# 3_-MCU_MAIN.net
KiCad netlist of a schematic drawn in Altium Designer
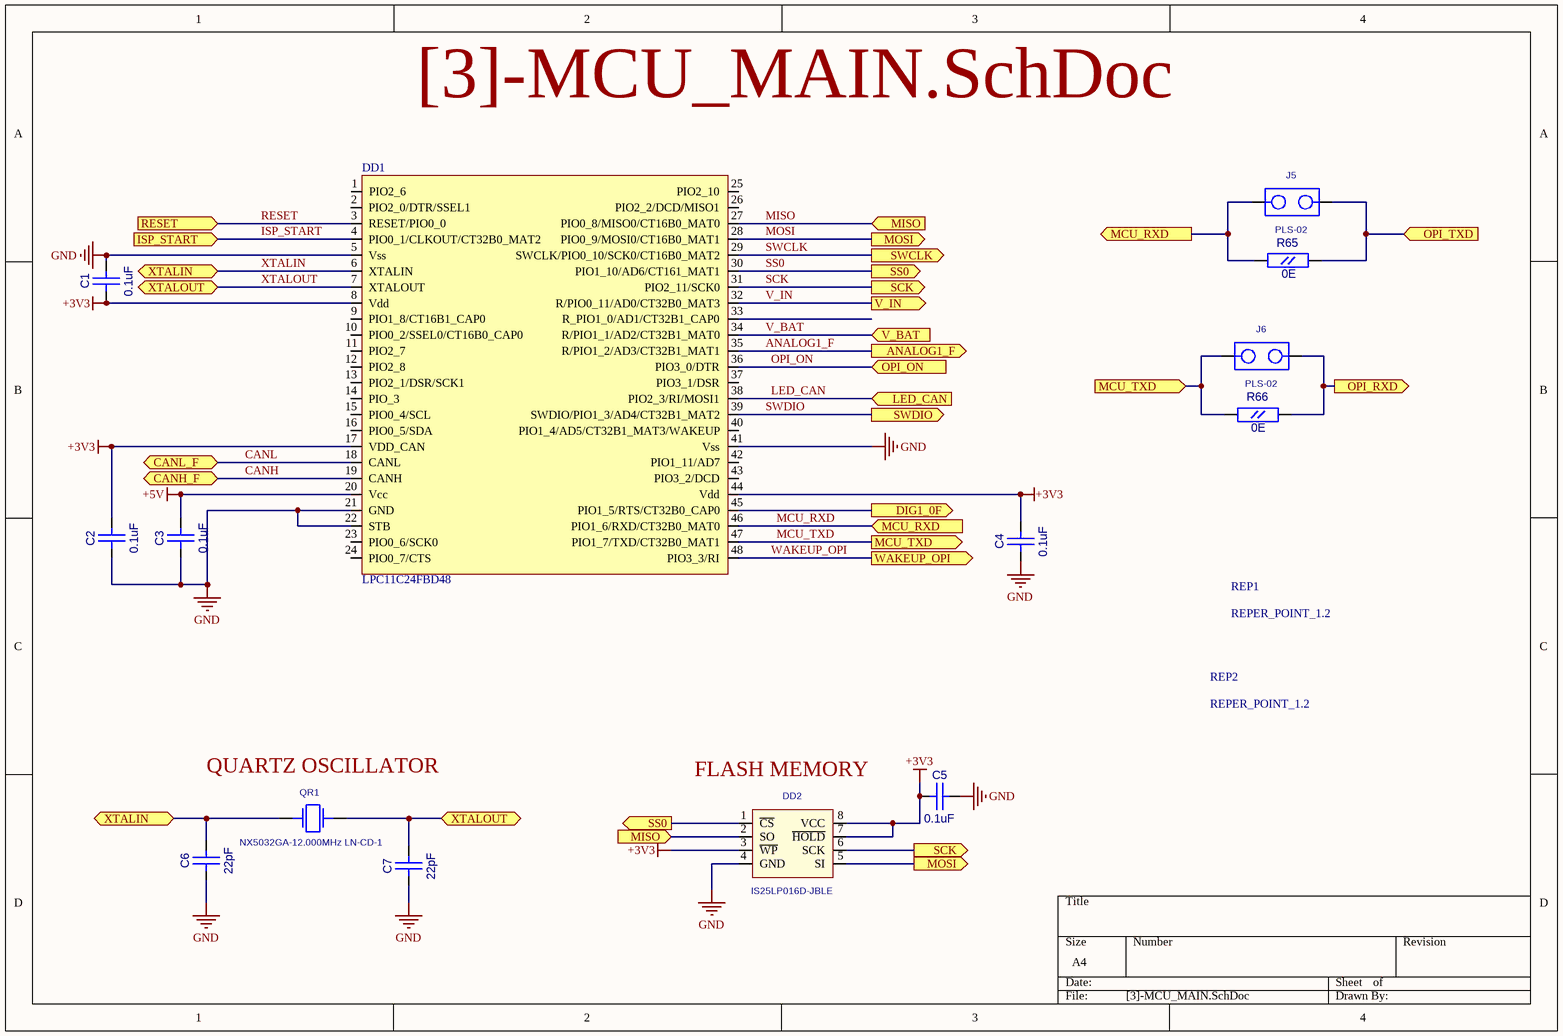
[diagram p0: [3]-MCU_MAIN.SchDoc]

(export (version "E")
  (design (tool "Eeschema 10.0.6"))
  (components
    (comp (ref "C1")
      (value "0.1uF")
      (footprint "CC0603")
      (description "CC0603")
      (libsource (lib "fizik_lib") (part "CC0603"))
    )
    (comp (ref "C2")
      (value "0.1uF")
      (footprint "CC0603")
      (description "CC0603")
      (libsource (lib "fizik_lib") (part "CC0603"))
    )
    (comp (ref "C3")
      (value "0.1uF")
      (footprint "CC0603")
      (description "CC0603")
      (libsource (lib "fizik_lib") (part "CC0603"))
    )
    (comp (ref "C4")
      (value "0.1uF")
      (footprint "CC0603")
      (description "CC0603")
      (libsource (lib "fizik_lib") (part "CC0603"))
    )
    (comp (ref "C5")
      (value "0.1uF")
      (footprint "CC0603")
      (description "CC0603")
      (libsource (lib "gprs_modem_2") (part "CC0603"))
    )
    (comp (ref "C6")
      (value "22pF")
      (footprint "CC0603")
      (description "CC0603")
      (libsource (lib "gprs_modem_2") (part "CC0603"))
    )
    (comp (ref "C7")
      (value "22pF")
      (footprint "CC0603")
      (description "CC0603")
      (libsource (lib "gprs_modem_2") (part "CC0603"))
    )
    (comp (ref "DD1")
      (value "LPC11C24FBD48")
      (footprint "LQFP48")
      (libsource (lib "fizik_lib") (part "LPC11C24FBD48"))
    )
    (comp (ref "DD2")
      (value "IS25LP016D-JBLE")
      (footprint "EIAJ_SO8")
      (description "S25FL016A0LMFI01")
      (libsource (lib "gprs_modem_2") (part "S25FL016A0LMFI01"))
    )
    (comp (ref "J5") (value "PLS-02") (footprint "PLS-02") (libsource (lib "fizik_lib") (part "PLS-02")))
    (comp (ref "J6") (value "PLS-02") (footprint "PLS-02") (libsource (lib "fizik_lib") (part "PLS-02")))
    (comp (ref "QR1")
      (value "NX5032GA-12.000MHz LN-CD-1")
      (footprint "AC5032_2")
      (description "AC5032/2")
      (libsource (lib "gprs_modem_2") (part "AC5032_2"))
    )
    (comp (ref "R65")
      (value "0E")
      (footprint "RC0603")
      (description "RC0603")
      (libsource (lib "fizik_lib") (part "RC0603"))
    )
    (comp (ref "R66")
      (value "0E")
      (footprint "RC0603")
      (description "RC0603")
      (libsource (lib "fizik_lib") (part "RC0603"))
    )
    (comp (ref "REP1")
      (value "REPER_POINT_1.2")
      (footprint "REPER1.2")
      (description "REPER1.2")
      (libsource (lib "fizik_lib") (part "REPER1.2"))
    )
    (comp (ref "REP2")
      (value "REPER_POINT_1.2")
      (footprint "REPER1.2")
      (description "REPER1.2")
      (libsource (lib "fizik_lib") (part "REPER1.2"))
    )
  )
  (nets
    (net (code "1") (name "+3V3") (class "Default")
      (node (ref "C1") (pin "1") (pinfunction "A_1") (pintype "passive"))
      (node (ref "C2") (pin "2") (pinfunction "B_2") (pintype "passive"))
      (node (ref "C4") (pin "2") (pinfunction "B_2") (pintype "passive"))
      (node (ref "C5") (pin "1") (pinfunction "A_1") (pintype "passive"))
      (node (ref "DD1") (pin "17") (pinfunction "VDD_CAN_17") (pintype "passive"))
      (node (ref "DD1") (pin "44") (pinfunction "Vdd_44") (pintype "passive"))
      (node (ref "DD1") (pin "8") (pinfunction "Vdd_8") (pintype "passive"))
      (node (ref "DD2") (pin "3") (pinfunction "~{WP}_3") (pintype "passive"))
      (node (ref "DD2") (pin "7") (pinfunction "~{HOLD}_7") (pintype "passive"))
      (node (ref "DD2") (pin "8") (pinfunction "VCC_8") (pintype "passive"))
    )
    (net (code "2") (name "+5V") (class "Default")
      (node (ref "C3") (pin "2") (pinfunction "B_2") (pintype "passive"))
      (node (ref "DD1") (pin "20") (pinfunction "Vcc_20") (pintype "passive"))
    )
    (net (code "3") (name "/ANALOG1_F") (class "Default")
      (node (ref "DD1") (pin "35") (pinfunction "R/PIO1_2/AD3/CT32B1_MAT1_35") (pintype "passive"))
    )
    (net (code "4") (name "/CANH") (class "Default")
      (node (ref "DD1") (pin "19") (pinfunction "CANH_19") (pintype "passive"))
    )
    (net (code "5") (name "/CANL") (class "Default")
      (node (ref "DD1") (pin "18") (pinfunction "CANL_18") (pintype "passive"))
    )
    (net (code "6") (name "/DIG1_0F") (class "Default")
      (node (ref "DD1") (pin "45") (pinfunction "PIO1_5/RTS/CT32B0_CAP0_45") (pintype "passive"))
    )
    (net (code "7") (name "/ISP_START") (class "Default")
      (node (ref "DD1") (pin "4") (pinfunction "PIO0_1/CLKOUT/CT32B0_MAT2_4") (pintype "passive"))
    )
    (net (code "8") (name "/LED_CAN") (class "Default")
      (node (ref "DD1") (pin "38") (pinfunction "PIO2_3/RI/MOSI1_38") (pintype "passive"))
    )
    (net (code "9") (name "/MCU_RXD") (class "Default")
      (node (ref "DD1") (pin "46") (pinfunction "PIO1_6/RXD/CT32B0_MAT0_46") (pintype "passive"))
      (node (ref "J5") (pin "1") (pintype "passive"))
      (node (ref "R65") (pin "1") (pinfunction "A_1") (pintype "passive"))
    )
    (net (code "10") (name "/MCU_TXD") (class "Default")
      (node (ref "DD1") (pin "47") (pinfunction "PIO1_7/TXD/CT32B0_MAT1_47") (pintype "passive"))
      (node (ref "J6") (pin "1") (pintype "passive"))
      (node (ref "R66") (pin "1") (pinfunction "A_1") (pintype "passive"))
    )
    (net (code "11") (name "/MISO") (class "Default")
      (node (ref "DD1") (pin "27") (pinfunction "PIO0_8/MISO0/CT16B0_MAT0_27") (pintype "passive"))
      (node (ref "DD2") (pin "2") (pinfunction "SO_2") (pintype "passive"))
    )
    (net (code "12") (name "/MOSI") (class "Default")
      (node (ref "DD1") (pin "28") (pinfunction "PIO0_9/MOSI0/CT16B0_MAT1_28") (pintype "passive"))
      (node (ref "DD2") (pin "5") (pinfunction "SI_5") (pintype "passive"))
    )
    (net (code "13") (name "/OPI_ON") (class "Default")
      (node (ref "DD1") (pin "36") (pinfunction "PIO3_0/DTR_36") (pintype "passive"))
    )
    (net (code "14") (name "/OPI_RXD") (class "Default")
      (node (ref "J6") (pin "2") (pintype "passive"))
      (node (ref "R66") (pin "2") (pinfunction "B_2") (pintype "passive"))
    )
    (net (code "15") (name "/OPI_TXD") (class "Default")
      (node (ref "J5") (pin "2") (pintype "passive"))
      (node (ref "R65") (pin "2") (pinfunction "B_2") (pintype "passive"))
    )
    (net (code "16") (name "/RESET") (class "Default")
      (node (ref "DD1") (pin "3") (pinfunction "RESET/PIO0_0_3") (pintype "passive"))
    )
    (net (code "17") (name "/SCK") (class "Default")
      (node (ref "DD1") (pin "31") (pinfunction "PIO2_11/SCK0_31") (pintype "passive"))
      (node (ref "DD2") (pin "6") (pinfunction "SCK_6") (pintype "passive"))
    )
    (net (code "18") (name "/SS0") (class "Default")
      (node (ref "DD1") (pin "30") (pinfunction "PIO1_10/AD6/CT161_MAT1_30") (pintype "passive"))
      (node (ref "DD2") (pin "1") (pinfunction "~{CS}_1") (pintype "passive"))
    )
    (net (code "19") (name "/SWCLK") (class "Default")
      (node (ref "DD1") (pin "29") (pinfunction "SWCLK/PIO0_10/SCK0/CT16B0_MAT2_29") (pintype "passive"))
    )
    (net (code "20") (name "/SWDIO") (class "Default")
      (node (ref "DD1") (pin "39") (pinfunction "SWDIO/PIO1_3/AD4/CT32B1_MAT2_39") (pintype "passive"))
    )
    (net (code "21") (name "/V_BAT") (class "Default")
      (node (ref "DD1") (pin "34") (pinfunction "R/PIO1_1/AD2/CT32B1_MAT0_34") (pintype "passive"))
    )
    (net (code "22") (name "/V_IN") (class "Default")
      (node (ref "DD1") (pin "32") (pinfunction "R/PIO0_11/AD0/CT32B0_MAT3_32") (pintype "passive"))
    )
    (net (code "23") (name "/WAKEUP_OPI") (class "Default")
      (node (ref "DD1") (pin "48") (pinfunction "PIO3_3/RI_48") (pintype "passive"))
    )
    (net (code "24") (name "/XTALIN") (class "Default")
      (node (ref "C6") (pin "2") (pinfunction "B_2") (pintype "passive"))
      (node (ref "DD1") (pin "6") (pinfunction "XTALIN_6") (pintype "passive"))
      (node (ref "QR1") (pin "1") (pintype "passive"))
    )
    (net (code "25") (name "/XTALOUT") (class "Default")
      (node (ref "C7") (pin "2") (pinfunction "B_2") (pintype "passive"))
      (node (ref "DD1") (pin "7") (pinfunction "XTALOUT_7") (pintype "passive"))
      (node (ref "QR1") (pin "2") (pintype "passive"))
    )
    (net (code "26") (name "GND") (class "Default")
      (node (ref "C1") (pin "2") (pinfunction "B_2") (pintype "passive"))
      (node (ref "C2") (pin "1") (pinfunction "A_1") (pintype "passive"))
      (node (ref "C3") (pin "1") (pinfunction "A_1") (pintype "passive"))
      (node (ref "C4") (pin "1") (pinfunction "A_1") (pintype "passive"))
      (node (ref "C5") (pin "2") (pinfunction "B_2") (pintype "passive"))
      (node (ref "C6") (pin "1") (pinfunction "A_1") (pintype "passive"))
      (node (ref "C7") (pin "1") (pinfunction "A_1") (pintype "passive"))
      (node (ref "DD1") (pin "21") (pinfunction "GND_21") (pintype "passive"))
      (node (ref "DD1") (pin "22") (pinfunction "STB_22") (pintype "passive"))
      (node (ref "DD1") (pin "41") (pinfunction "Vss_41") (pintype "passive"))
      (node (ref "DD1") (pin "5") (pinfunction "Vss_5") (pintype "passive"))
      (node (ref "DD2") (pin "4") (pinfunction "GND_4") (pintype "passive"))
    )
    (net (code "27") (name "unconnected-(DD1-PIO0_2{slash}SSEL0{slash}CT16B0_CAP0-Pad10)") (class "Default")
      (node (ref "DD1") (pin "10") (pinfunction "PIO0_2/SSEL0/CT16B0_CAP0_10") (pintype "passive"))
    )
    (net (code "28") (name "unconnected-(DD1-PIO0_4{slash}SCL-Pad15)") (class "Default")
      (node (ref "DD1") (pin "15") (pinfunction "PIO0_4/SCL_15") (pintype "passive"))
    )
    (net (code "29") (name "unconnected-(DD1-PIO0_5{slash}SDA-Pad16)") (class "Default")
      (node (ref "DD1") (pin "16") (pinfunction "PIO0_5/SDA_16") (pintype "passive"))
    )
    (net (code "30") (name "unconnected-(DD1-PIO0_6{slash}SCK0-Pad23)") (class "Default")
      (node (ref "DD1") (pin "23") (pinfunction "PIO0_6/SCK0_23") (pintype "passive"))
    )
    (net (code "31") (name "unconnected-(DD1-PIO0_7{slash}CTS-Pad24)") (class "Default")
      (node (ref "DD1") (pin "24") (pinfunction "PIO0_7/CTS_24") (pintype "passive"))
    )
    (net (code "32") (name "unconnected-(DD1-PIO1_4{slash}AD5{slash}CT32B1_MAT3{slash}WAKEUP-Pad40)") (class "Default")
      (node (ref "DD1") (pin "40") (pinfunction "PIO1_4/AD5/CT32B1_MAT3/WAKEUP_40") (pintype "passive"))
    )
    (net (code "33") (name "unconnected-(DD1-PIO1_8{slash}CT16B1_CAP0-Pad9)") (class "Default")
      (node (ref "DD1") (pin "9") (pinfunction "PIO1_8/CT16B1_CAP0_9") (pintype "passive"))
    )
    (net (code "34") (name "unconnected-(DD1-PIO1_11{slash}AD7-Pad42)") (class "Default")
      (node (ref "DD1") (pin "42") (pinfunction "PIO1_11/AD7_42") (pintype "passive"))
    )
    (net (code "35") (name "unconnected-(DD1-PIO2_0{slash}DTR{slash}SSEL1-Pad2)") (class "Default")
      (node (ref "DD1") (pin "2") (pinfunction "PIO2_0/DTR/SSEL1_2") (pintype "passive"))
    )
    (net (code "36") (name "unconnected-(DD1-PIO2_1{slash}DSR{slash}SCK1-Pad13)") (class "Default")
      (node (ref "DD1") (pin "13") (pinfunction "PIO2_1/DSR/SCK1_13") (pintype "passive"))
    )
    (net (code "37") (name "unconnected-(DD1-PIO2_2{slash}DCD{slash}MISO1-Pad26)") (class "Default")
      (node (ref "DD1") (pin "26") (pinfunction "PIO2_2/DCD/MISO1_26") (pintype "passive"))
    )
    (net (code "38") (name "unconnected-(DD1-PIO2_6-Pad1)") (class "Default")
      (node (ref "DD1") (pin "1") (pinfunction "PIO2_6_1") (pintype "passive"))
    )
    (net (code "39") (name "unconnected-(DD1-PIO2_7-Pad11)") (class "Default")
      (node (ref "DD1") (pin "11") (pinfunction "PIO2_7_11") (pintype "passive"))
    )
    (net (code "40") (name "unconnected-(DD1-PIO2_8-Pad12)") (class "Default")
      (node (ref "DD1") (pin "12") (pinfunction "PIO2_8_12") (pintype "passive"))
    )
    (net (code "41") (name "unconnected-(DD1-PIO2_10-Pad25)") (class "Default")
      (node (ref "DD1") (pin "25") (pinfunction "PIO2_10_25") (pintype "passive"))
    )
    (net (code "42") (name "unconnected-(DD1-PIO3_1{slash}DSR-Pad37)") (class "Default")
      (node (ref "DD1") (pin "37") (pinfunction "PIO3_1/DSR_37") (pintype "passive"))
    )
    (net (code "43") (name "unconnected-(DD1-PIO3_2{slash}DCD-Pad43)") (class "Default")
      (node (ref "DD1") (pin "43") (pinfunction "PIO3_2/DCD_43") (pintype "passive"))
    )
    (net (code "44") (name "unconnected-(DD1-PIO_3-Pad14)") (class "Default")
      (node (ref "DD1") (pin "14") (pinfunction "PIO_3_14") (pintype "passive"))
    )
    (net (code "45") (name "unconnected-(DD1-R_PIO1_0{slash}AD1{slash}CT32B1_CAP0-Pad33)") (class "Default")
      (node (ref "DD1") (pin "33") (pinfunction "R_PIO1_0/AD1/CT32B1_CAP0_33") (pintype "passive"))
    )
    (net (code "46") (name "unconnected-(REP1-Pad1)") (class "Default")
      (node (ref "REP1") (pin "1") (pintype "passive"))
    )
    (net (code "47") (name "unconnected-(REP2-Pad1)") (class "Default")
      (node (ref "REP2") (pin "1") (pintype "passive"))
    )
  )
)
